# SECONDARY_MODULE.net
KiCad netlist of a schematic drawn in EAGLE
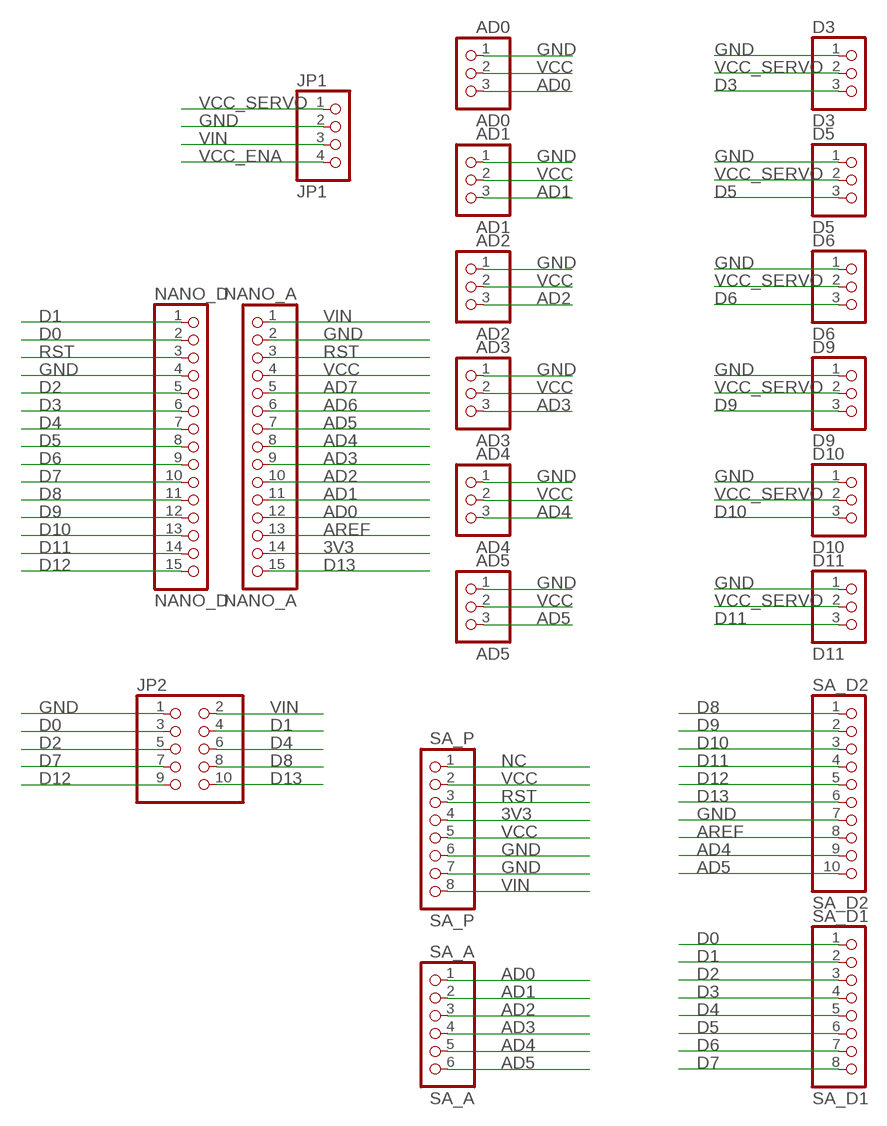
[diagram p0: schematic, sheet 1]

(export (version "E")
  (design (tool "Eeschema 10.0.6"))
  (components
    (comp (ref "AD0")
      (value "AD0")
      (footprint "eagle-import:1X03")
      (libsource (lib "eagle-import") (part "PINHD-1X3"))
    )
    (comp (ref "AD1")
      (value "AD1")
      (footprint "eagle-import:1X03")
      (libsource (lib "eagle-import") (part "PINHD-1X3"))
    )
    (comp (ref "AD2")
      (value "AD2")
      (footprint "eagle-import:1X03")
      (libsource (lib "eagle-import") (part "PINHD-1X3"))
    )
    (comp (ref "AD3")
      (value "AD3")
      (footprint "eagle-import:1X03")
      (libsource (lib "eagle-import") (part "PINHD-1X3"))
    )
    (comp (ref "AD4")
      (value "AD4")
      (footprint "eagle-import:1X03")
      (libsource (lib "eagle-import") (part "PINHD-1X3"))
    )
    (comp (ref "AD5")
      (value "AD5")
      (footprint "eagle-import:1X03")
      (libsource (lib "eagle-import") (part "PINHD-1X3"))
    )
    (comp (ref "D3")
      (value "D3")
      (footprint "eagle-import:1X03")
      (libsource (lib "eagle-import") (part "PINHD-1X3"))
    )
    (comp (ref "D5")
      (value "D5")
      (footprint "eagle-import:1X03")
      (libsource (lib "eagle-import") (part "PINHD-1X3"))
    )
    (comp (ref "D6")
      (value "D6")
      (footprint "eagle-import:1X03")
      (libsource (lib "eagle-import") (part "PINHD-1X3"))
    )
    (comp (ref "D9")
      (value "D9")
      (footprint "eagle-import:1X03")
      (libsource (lib "eagle-import") (part "PINHD-1X3"))
    )
    (comp (ref "D10")
      (value "D10")
      (footprint "eagle-import:1X03")
      (libsource (lib "eagle-import") (part "PINHD-1X3"))
    )
    (comp (ref "D11")
      (value "D11")
      (footprint "eagle-import:1X03")
      (libsource (lib "eagle-import") (part "PINHD-1X3"))
    )
    (comp (ref "JP1")
      (value "JP1")
      (footprint "eagle-import:1X04")
      (libsource (lib "eagle-import") (part "PINHD-1X4"))
    )
    (comp (ref "JP2")
      (value "PINHD-2X5")
      (footprint "eagle-import:2X05")
      (libsource (lib "eagle-import") (part "PINHD-2X5"))
    )
    (comp (ref "NANO_A")
      (value "NANO_A")
      (footprint "eagle-import:1X15")
      (libsource (lib "eagle-import") (part "PINHD-1X15"))
    )
    (comp (ref "NANO_D")
      (value "NANO_D")
      (footprint "eagle-import:1X15")
      (libsource (lib "eagle-import") (part "PINHD-1X15"))
    )
    (comp (ref "SA_A")
      (value "SA_A")
      (footprint "eagle-import:1X06")
      (libsource (lib "eagle-import") (part "PINHD-1X6"))
    )
    (comp (ref "SA_D1")
      (value "SA_D1")
      (footprint "eagle-import:1X08")
      (libsource (lib "eagle-import") (part "PINHD-1X8"))
    )
    (comp (ref "SA_D2")
      (value "SA_D2")
      (footprint "eagle-import:1X10")
      (libsource (lib "eagle-import") (part "PINHD-1X10"))
    )
    (comp (ref "SA_P")
      (value "SA_P")
      (footprint "eagle-import:1X08")
      (libsource (lib "eagle-import") (part "PINHD-1X8"))
    )
  )
  (nets
    (net (code "1") (name "/3V3") (class "Default")
      (node (ref "NANO_A") (pin "14") (pinfunction "14_14") (pintype "passive"))
      (node (ref "SA_P") (pin "4") (pinfunction "4_4") (pintype "passive"))
    )
    (net (code "2") (name "/AD0") (class "Default")
      (node (ref "AD0") (pin "3") (pinfunction "3_3") (pintype "passive"))
      (node (ref "NANO_A") (pin "12") (pinfunction "12_12") (pintype "passive"))
      (node (ref "SA_A") (pin "1") (pinfunction "1_1") (pintype "passive"))
    )
    (net (code "3") (name "/AD1") (class "Default")
      (node (ref "AD1") (pin "3") (pinfunction "3_3") (pintype "passive"))
      (node (ref "NANO_A") (pin "11") (pinfunction "11_11") (pintype "passive"))
      (node (ref "SA_A") (pin "2") (pinfunction "2_2") (pintype "passive"))
    )
    (net (code "4") (name "/AD2") (class "Default")
      (node (ref "AD2") (pin "3") (pinfunction "3_3") (pintype "passive"))
      (node (ref "NANO_A") (pin "10") (pinfunction "10_10") (pintype "passive"))
      (node (ref "SA_A") (pin "3") (pinfunction "3_3") (pintype "passive"))
    )
    (net (code "5") (name "/AD3") (class "Default")
      (node (ref "AD3") (pin "3") (pinfunction "3_3") (pintype "passive"))
      (node (ref "NANO_A") (pin "9") (pinfunction "9_9") (pintype "passive"))
      (node (ref "SA_A") (pin "4") (pinfunction "4_4") (pintype "passive"))
    )
    (net (code "6") (name "/AD4") (class "Default")
      (node (ref "AD4") (pin "3") (pinfunction "3_3") (pintype "passive"))
      (node (ref "NANO_A") (pin "8") (pinfunction "8_8") (pintype "passive"))
      (node (ref "SA_A") (pin "5") (pinfunction "5_5") (pintype "passive"))
      (node (ref "SA_D2") (pin "9") (pinfunction "9_9") (pintype "passive"))
    )
    (net (code "7") (name "/AD5") (class "Default")
      (node (ref "AD5") (pin "3") (pinfunction "3_3") (pintype "passive"))
      (node (ref "NANO_A") (pin "7") (pinfunction "7_7") (pintype "passive"))
      (node (ref "SA_A") (pin "6") (pinfunction "6_6") (pintype "passive"))
      (node (ref "SA_D2") (pin "10") (pinfunction "10_10") (pintype "passive"))
    )
    (net (code "8") (name "/AD6") (class "Default")
      (node (ref "NANO_A") (pin "6") (pinfunction "6_6") (pintype "passive"))
    )
    (net (code "9") (name "/AD7") (class "Default")
      (node (ref "NANO_A") (pin "5") (pinfunction "5_5") (pintype "passive"))
    )
    (net (code "10") (name "/AREF") (class "Default")
      (node (ref "NANO_A") (pin "13") (pinfunction "13_13") (pintype "passive"))
      (node (ref "SA_D2") (pin "8") (pinfunction "8_8") (pintype "passive"))
    )
    (net (code "11") (name "/D0") (class "Default")
      (node (ref "JP2") (pin "3") (pinfunction "3_3") (pintype "passive"))
      (node (ref "NANO_D") (pin "2") (pinfunction "2_2") (pintype "passive"))
      (node (ref "SA_D1") (pin "1") (pinfunction "1_1") (pintype "passive"))
    )
    (net (code "12") (name "/D1") (class "Default")
      (node (ref "JP2") (pin "4") (pinfunction "4_4") (pintype "passive"))
      (node (ref "NANO_D") (pin "1") (pinfunction "1_1") (pintype "passive"))
      (node (ref "SA_D1") (pin "2") (pinfunction "2_2") (pintype "passive"))
    )
    (net (code "13") (name "/D2") (class "Default")
      (node (ref "JP2") (pin "5") (pinfunction "5_5") (pintype "passive"))
      (node (ref "NANO_D") (pin "5") (pinfunction "5_5") (pintype "passive"))
      (node (ref "SA_D1") (pin "3") (pinfunction "3_3") (pintype "passive"))
    )
    (net (code "14") (name "/D3") (class "Default")
      (node (ref "D3") (pin "3") (pinfunction "3_3") (pintype "passive"))
      (node (ref "NANO_D") (pin "6") (pinfunction "6_6") (pintype "passive"))
      (node (ref "SA_D1") (pin "4") (pinfunction "4_4") (pintype "passive"))
    )
    (net (code "15") (name "/D4") (class "Default")
      (node (ref "JP2") (pin "6") (pinfunction "6_6") (pintype "passive"))
      (node (ref "NANO_D") (pin "7") (pinfunction "7_7") (pintype "passive"))
      (node (ref "SA_D1") (pin "5") (pinfunction "5_5") (pintype "passive"))
    )
    (net (code "16") (name "/D5") (class "Default")
      (node (ref "D5") (pin "3") (pinfunction "3_3") (pintype "passive"))
      (node (ref "NANO_D") (pin "8") (pinfunction "8_8") (pintype "passive"))
      (node (ref "SA_D1") (pin "6") (pinfunction "6_6") (pintype "passive"))
    )
    (net (code "17") (name "/D6") (class "Default")
      (node (ref "D6") (pin "3") (pinfunction "3_3") (pintype "passive"))
      (node (ref "NANO_D") (pin "9") (pinfunction "9_9") (pintype "passive"))
      (node (ref "SA_D1") (pin "7") (pinfunction "7_7") (pintype "passive"))
    )
    (net (code "18") (name "/D7") (class "Default")
      (node (ref "JP2") (pin "7") (pinfunction "7_7") (pintype "passive"))
      (node (ref "NANO_D") (pin "10") (pinfunction "10_10") (pintype "passive"))
      (node (ref "SA_D1") (pin "8") (pinfunction "8_8") (pintype "passive"))
    )
    (net (code "19") (name "/D8") (class "Default")
      (node (ref "JP2") (pin "8") (pinfunction "8_8") (pintype "passive"))
      (node (ref "NANO_D") (pin "11") (pinfunction "11_11") (pintype "passive"))
      (node (ref "SA_D2") (pin "1") (pinfunction "1_1") (pintype "passive"))
    )
    (net (code "20") (name "/D9") (class "Default")
      (node (ref "D9") (pin "3") (pinfunction "3_3") (pintype "passive"))
      (node (ref "NANO_D") (pin "12") (pinfunction "12_12") (pintype "passive"))
      (node (ref "SA_D2") (pin "2") (pinfunction "2_2") (pintype "passive"))
    )
    (net (code "21") (name "/D10") (class "Default")
      (node (ref "D10") (pin "3") (pinfunction "3_3") (pintype "passive"))
      (node (ref "NANO_D") (pin "13") (pinfunction "13_13") (pintype "passive"))
      (node (ref "SA_D2") (pin "3") (pinfunction "3_3") (pintype "passive"))
    )
    (net (code "22") (name "/D11") (class "Default")
      (node (ref "D11") (pin "3") (pinfunction "3_3") (pintype "passive"))
      (node (ref "NANO_D") (pin "14") (pinfunction "14_14") (pintype "passive"))
      (node (ref "SA_D2") (pin "4") (pinfunction "4_4") (pintype "passive"))
    )
    (net (code "23") (name "/D12") (class "Default")
      (node (ref "JP2") (pin "9") (pinfunction "9_9") (pintype "passive"))
      (node (ref "NANO_D") (pin "15") (pinfunction "15_15") (pintype "passive"))
      (node (ref "SA_D2") (pin "5") (pinfunction "5_5") (pintype "passive"))
    )
    (net (code "24") (name "/D13") (class "Default")
      (node (ref "JP2") (pin "10") (pinfunction "10_10") (pintype "passive"))
      (node (ref "NANO_A") (pin "15") (pinfunction "15_15") (pintype "passive"))
      (node (ref "SA_D2") (pin "6") (pinfunction "6_6") (pintype "passive"))
    )
    (net (code "25") (name "/GND") (class "Default")
      (node (ref "AD0") (pin "1") (pinfunction "1_1") (pintype "passive"))
      (node (ref "AD1") (pin "1") (pinfunction "1_1") (pintype "passive"))
      (node (ref "AD2") (pin "1") (pinfunction "1_1") (pintype "passive"))
      (node (ref "AD3") (pin "1") (pinfunction "1_1") (pintype "passive"))
      (node (ref "AD4") (pin "1") (pinfunction "1_1") (pintype "passive"))
      (node (ref "AD5") (pin "1") (pinfunction "1_1") (pintype "passive"))
      (node (ref "D10") (pin "1") (pinfunction "1_1") (pintype "passive"))
      (node (ref "D11") (pin "1") (pinfunction "1_1") (pintype "passive"))
      (node (ref "D3") (pin "1") (pinfunction "1_1") (pintype "passive"))
      (node (ref "D5") (pin "1") (pinfunction "1_1") (pintype "passive"))
      (node (ref "D6") (pin "1") (pinfunction "1_1") (pintype "passive"))
      (node (ref "D9") (pin "1") (pinfunction "1_1") (pintype "passive"))
      (node (ref "JP1") (pin "2") (pinfunction "2_2") (pintype "passive"))
      (node (ref "JP2") (pin "1") (pinfunction "1_1") (pintype "passive"))
      (node (ref "NANO_A") (pin "2") (pinfunction "2_2") (pintype "passive"))
      (node (ref "NANO_D") (pin "4") (pinfunction "4_4") (pintype "passive"))
      (node (ref "SA_D2") (pin "7") (pinfunction "7_7") (pintype "passive"))
      (node (ref "SA_P") (pin "6") (pinfunction "6_6") (pintype "passive"))
      (node (ref "SA_P") (pin "7") (pinfunction "7_7") (pintype "passive"))
    )
    (net (code "26") (name "/NC") (class "Default")
      (node (ref "SA_P") (pin "1") (pinfunction "1_1") (pintype "passive"))
    )
    (net (code "27") (name "/RST") (class "Default")
      (node (ref "NANO_A") (pin "3") (pinfunction "3_3") (pintype "passive"))
      (node (ref "NANO_D") (pin "3") (pinfunction "3_3") (pintype "passive"))
      (node (ref "SA_P") (pin "3") (pinfunction "3_3") (pintype "passive"))
    )
    (net (code "28") (name "/VCC") (class "Default")
      (node (ref "AD0") (pin "2") (pinfunction "2_2") (pintype "passive"))
      (node (ref "AD1") (pin "2") (pinfunction "2_2") (pintype "passive"))
      (node (ref "AD2") (pin "2") (pinfunction "2_2") (pintype "passive"))
      (node (ref "AD3") (pin "2") (pinfunction "2_2") (pintype "passive"))
      (node (ref "AD4") (pin "2") (pinfunction "2_2") (pintype "passive"))
      (node (ref "AD5") (pin "2") (pinfunction "2_2") (pintype "passive"))
      (node (ref "NANO_A") (pin "4") (pinfunction "4_4") (pintype "passive"))
      (node (ref "SA_P") (pin "2") (pinfunction "2_2") (pintype "passive"))
      (node (ref "SA_P") (pin "5") (pinfunction "5_5") (pintype "passive"))
    )
    (net (code "29") (name "/VCC_ENA") (class "Default")
      (node (ref "JP1") (pin "4") (pinfunction "4_4") (pintype "passive"))
    )
    (net (code "30") (name "/VCC_SERVO") (class "Default")
      (node (ref "D10") (pin "2") (pinfunction "2_2") (pintype "passive"))
      (node (ref "D11") (pin "2") (pinfunction "2_2") (pintype "passive"))
      (node (ref "D3") (pin "2") (pinfunction "2_2") (pintype "passive"))
      (node (ref "D5") (pin "2") (pinfunction "2_2") (pintype "passive"))
      (node (ref "D6") (pin "2") (pinfunction "2_2") (pintype "passive"))
      (node (ref "D9") (pin "2") (pinfunction "2_2") (pintype "passive"))
      (node (ref "JP1") (pin "1") (pinfunction "1_1") (pintype "passive"))
    )
    (net (code "31") (name "/VIN") (class "Default")
      (node (ref "JP1") (pin "3") (pinfunction "3_3") (pintype "passive"))
      (node (ref "JP2") (pin "2") (pinfunction "2_2") (pintype "passive"))
      (node (ref "NANO_A") (pin "1") (pinfunction "1_1") (pintype "passive"))
      (node (ref "SA_P") (pin "8") (pinfunction "8_8") (pintype "passive"))
    )
  )
)
